# arduino_uno_pcb__with_lcd.net
KiCad netlist of a schematic drawn in EAGLE
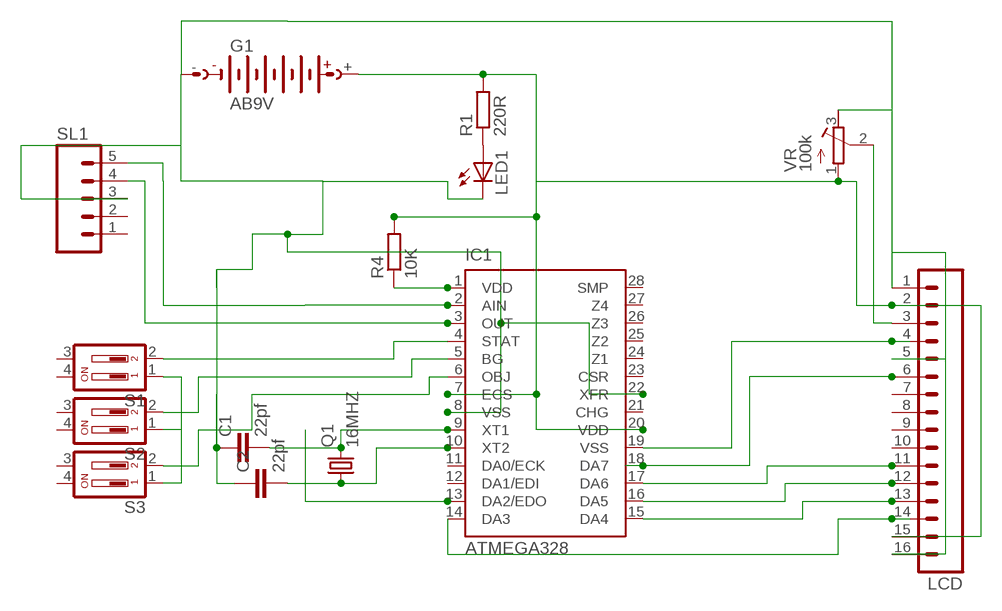
[diagram p0: schematic, sheet 1]

(export (version "E")
  (design (tool "Eeschema 10.0.6"))
  (components
    (comp (ref "C1")
      (value "22pf")
      (footprint "eagle-import:C2.5-2")
      (libsource (lib "eagle-import") (part "C2.5/2"))
    )
    (comp (ref "C2")
      (value "22pf")
      (footprint "eagle-import:C2.5-2")
      (libsource (lib "eagle-import") (part "C2.5/2"))
    )
    (comp (ref "G1")
      (value "AB9V")
      (footprint "eagle-import:AB9V")
      (libsource (lib "eagle-import") (part "AB9V"))
    )
    (comp (ref "IC1")
      (value "ATMEGA328")
      (footprint "eagle-import:DIL28-3")
      (libsource (lib "eagle-import") (part "QT9701BD"))
    )
    (comp (ref "LCD")
      (value "M16")
      (footprint "eagle-import:16P")
      (libsource (lib "eagle-import") (part "M16"))
    )
    (comp (ref "LED1")
      (value "LED3MM")
      (footprint "eagle-import:LED3MM")
      (libsource (lib "eagle-import") (part "LED3MM"))
    )
    (comp (ref "Q1")
      (value "16MHZ")
      (footprint "eagle-import:HC49_S")
      (libsource (lib "eagle-import") (part "CRYSTALHC49S"))
    )
    (comp (ref "R1")
      (value "220R")
      (footprint "eagle-import:0207_10")
      (libsource (lib "eagle-import") (part "R-EU_0207/10"))
    )
    (comp (ref "R4")
      (value "10K")
      (footprint "eagle-import:0207_10")
      (libsource (lib "eagle-import") (part "R-EU_0207/10"))
    )
    (comp (ref "S1")
      (value "DP02")
      (footprint "eagle-import:DP-02")
      (fields (field (name "MPN") "MCDP02"))
      (libsource (lib "eagle-import") (part "DP02"))
    )
    (comp (ref "S2")
      (value "DP02")
      (footprint "eagle-import:DP-02")
      (fields
        (field (name "MPN") "MCDP02")
        (field (name "MPN_1") "MCDP02")
        (field (name "OC_FARNELL") "1255233")
        (field (name "OC_NEWARK") "26M1095")
      )
      (libsource (lib "eagle-import") (part "DP02"))
    )
    (comp (ref "S3")
      (value "DP02")
      (footprint "eagle-import:DP-02")
      (fields
        (field (name "MPN") "MCDP02")
        (field (name "MPN_1") "MCDP02")
        (field (name "OC_FARNELL") "1255233")
        (field (name "OC_NEWARK") "26M1095")
      )
      (libsource (lib "eagle-import") (part "DP02"))
    )
    (comp (ref "SL1")
      (value "M05")
      (footprint "eagle-import:05P")
      (libsource (lib "eagle-import") (part "M05"))
    )
    (comp (ref "VR")
      (value "100k")
      (footprint "eagle-import:RTRIM64P")
      (libsource (lib "eagle-import") (part "R-TRIMM64P"))
    )
  )
  (nets
    (net (code "1") (name "Net-(IC1-AIN)") (class "Default")
      (node (ref "IC1") (pin "2") (pinfunction "AIN_2") (pintype "input"))
      (node (ref "SL1") (pin "5") (pinfunction "5_5") (pintype "passive"))
    )
    (net (code "2") (name "Net-(IC1-BG)") (class "Default")
      (node (ref "IC1") (pin "5") (pinfunction "BG_5") (pintype "input"))
      (node (ref "S2") (pin "2") (pinfunction "2_2") (pintype "passive"))
    )
    (net (code "3") (name "Net-(IC1-DA3)") (class "Default")
      (node (ref "IC1") (pin "14") (pinfunction "DA3_14") (pintype "output"))
      (node (ref "LCD") (pin "14") (pinfunction "14_14") (pintype "passive"))
    )
    (net (code "4") (name "Net-(IC1-DA4)") (class "Default")
      (node (ref "IC1") (pin "15") (pinfunction "DA4_15") (pintype "output"))
      (node (ref "LCD") (pin "13") (pinfunction "13_13") (pintype "passive"))
    )
    (net (code "5") (name "Net-(IC1-DA5)") (class "Default")
      (node (ref "IC1") (pin "16") (pinfunction "DA5_16") (pintype "output"))
      (node (ref "LCD") (pin "12") (pinfunction "12_12") (pintype "passive"))
    )
    (net (code "6") (name "Net-(IC1-DA6)") (class "Default")
      (node (ref "IC1") (pin "17") (pinfunction "DA6_17") (pintype "output"))
      (node (ref "LCD") (pin "11") (pinfunction "11_11") (pintype "passive"))
    )
    (net (code "7") (name "Net-(IC1-DA7)") (class "Default")
      (node (ref "IC1") (pin "18") (pinfunction "DA7_18") (pintype "output"))
      (node (ref "LCD") (pin "6") (pinfunction "6_6") (pintype "passive"))
    )
    (net (code "8") (name "Net-(IC1-ECS)") (class "Default")
      (node (ref "G1") (pin "+") (pinfunction "+_+") (pintype "passive"))
      (node (ref "IC1") (pin "20") (pinfunction "VDD_20") (pintype "input"))
      (node (ref "IC1") (pin "7") (pinfunction "ECS_7") (pintype "output"))
      (node (ref "LCD") (pin "15") (pinfunction "15_15") (pintype "passive"))
      (node (ref "LCD") (pin "2") (pinfunction "2_2") (pintype "passive"))
      (node (ref "R1") (pin "2") (pinfunction "2_2") (pintype "passive"))
      (node (ref "R4") (pin "2") (pinfunction "2_2") (pintype "passive"))
      (node (ref "VR") (pin "1") (pinfunction "E_1") (pintype "passive"))
    )
    (net (code "9") (name "Net-(IC1-OBJ)") (class "Default")
      (node (ref "IC1") (pin "6") (pinfunction "OBJ_6") (pintype "input"))
      (node (ref "S3") (pin "2") (pinfunction "2_2") (pintype "passive"))
    )
    (net (code "10") (name "Net-(IC1-OUT)") (class "Default")
      (node (ref "IC1") (pin "3") (pinfunction "OUT_3") (pintype "output"))
      (node (ref "SL1") (pin "4") (pinfunction "4_4") (pintype "passive"))
    )
    (net (code "11") (name "Net-(IC1-STAT)") (class "Default")
      (node (ref "IC1") (pin "4") (pinfunction "STAT_4") (pintype "output"))
      (node (ref "S1") (pin "2") (pinfunction "2_2") (pintype "passive"))
    )
    (net (code "12") (name "Net-(IC1-VDD-Pad1)") (class "Default")
      (node (ref "IC1") (pin "1") (pinfunction "VDD_1") (pintype "input"))
      (node (ref "R4") (pin "1") (pinfunction "1_1") (pintype "passive"))
    )
    (net (code "13") (name "Net-(IC1-VSS-Pad19)") (class "Default")
      (node (ref "IC1") (pin "19") (pinfunction "VSS_19") (pintype "input"))
      (node (ref "LCD") (pin "4") (pinfunction "4_4") (pintype "passive"))
    )
    (net (code "14") (name "Net-(IC1-XFR)") (class "Default")
      (node (ref "C1") (pin "1") (pinfunction "1_1") (pintype "passive"))
      (node (ref "C2") (pin "1") (pinfunction "1_1") (pintype "passive"))
      (node (ref "G1") (pin "-") (pinfunction "-_-") (pintype "passive"))
      (node (ref "IC1") (pin "22") (pinfunction "XFR_22") (pintype "output"))
      (node (ref "IC1") (pin "8") (pinfunction "VSS_8") (pintype "input"))
      (node (ref "LCD") (pin "1") (pinfunction "1_1") (pintype "passive"))
      (node (ref "LCD") (pin "16") (pinfunction "16_16") (pintype "passive"))
      (node (ref "LCD") (pin "5") (pinfunction "5_5") (pintype "passive"))
      (node (ref "LED1") (pin "K") (pinfunction "C_K") (pintype "passive"))
      (node (ref "SL1") (pin "3") (pinfunction "3_3") (pintype "passive"))
      (node (ref "VR") (pin "3") (pinfunction "A_3") (pintype "passive"))
    )
    (net (code "15") (name "Net-(IC1-XT1)") (class "Default")
      (node (ref "C1") (pin "2") (pinfunction "2_2") (pintype "passive"))
      (node (ref "IC1") (pin "9") (pinfunction "XT1_9") (pintype "input"))
      (node (ref "Q1") (pin "2") (pinfunction "2_2") (pintype "passive"))
    )
    (net (code "16") (name "Net-(IC1-XT2)") (class "Default")
      (node (ref "C2") (pin "2") (pinfunction "2_2") (pintype "passive"))
      (node (ref "IC1") (pin "10") (pinfunction "XT2_10") (pintype "output"))
      (node (ref "Q1") (pin "1") (pinfunction "1_1") (pintype "passive"))
    )
    (net (code "17") (name "Net-(LED1-PadA)") (class "Default")
      (node (ref "LED1") (pin "A") (pinfunction "A_A") (pintype "passive"))
      (node (ref "R1") (pin "1") (pinfunction "1_1") (pintype "passive"))
    )
    (net (code "18") (name "Net-(S1-Pad1)") (class "Default")
      (node (ref "S1") (pin "1") (pinfunction "1_1") (pintype "passive"))
      (node (ref "S2") (pin "1") (pinfunction "1_1") (pintype "passive"))
      (node (ref "S3") (pin "1") (pinfunction "1_1") (pintype "passive"))
    )
    (net (code "19") (name "Net-(VR-S)") (class "Default")
      (node (ref "LCD") (pin "3") (pinfunction "3_3") (pintype "passive"))
      (node (ref "VR") (pin "2") (pinfunction "S_2") (pintype "passive"))
    )
    (net (code "20") (name "unconnected-(IC1-CHG-Pad21)") (class "Default")
      (node (ref "IC1") (pin "21") (pinfunction "CHG_21") (pintype "output"))
    )
    (net (code "21") (name "unconnected-(IC1-CSR-Pad23)") (class "Default")
      (node (ref "IC1") (pin "23") (pinfunction "CSR_23") (pintype "output"))
    )
    (net (code "22") (name "unconnected-(IC1-DA0{slash}ECK-Pad11)") (class "Default")
      (node (ref "IC1") (pin "11") (pinfunction "DA0/ECK_11") (pintype "output"))
    )
    (net (code "23") (name "unconnected-(IC1-DA1{slash}EDI-Pad12)") (class "Default")
      (node (ref "IC1") (pin "12") (pinfunction "DA1/EDI_12") (pintype "output"))
    )
    (net (code "24") (name "unconnected-(IC1-DA2{slash}EDO-Pad13)") (class "Default")
      (node (ref "IC1") (pin "13") (pinfunction "DA2/EDO_13") (pintype "output"))
    )
    (net (code "25") (name "unconnected-(IC1-SMP-Pad28)") (class "Default")
      (node (ref "IC1") (pin "28") (pinfunction "SMP_28") (pintype "output"))
    )
    (net (code "26") (name "unconnected-(IC1-Z1-Pad24)") (class "Default")
      (node (ref "IC1") (pin "24") (pinfunction "Z1_24") (pintype "output"))
    )
    (net (code "27") (name "unconnected-(IC1-Z2-Pad25)") (class "Default")
      (node (ref "IC1") (pin "25") (pinfunction "Z2_25") (pintype "output"))
    )
    (net (code "28") (name "unconnected-(IC1-Z3-Pad26)") (class "Default")
      (node (ref "IC1") (pin "26") (pinfunction "Z3_26") (pintype "output"))
    )
    (net (code "29") (name "unconnected-(IC1-Z4-Pad27)") (class "Default")
      (node (ref "IC1") (pin "27") (pinfunction "Z4_27") (pintype "output"))
    )
    (net (code "30") (name "unconnected-(LCD-Pad7)") (class "Default")
      (node (ref "LCD") (pin "7") (pinfunction "7_7") (pintype "passive"))
    )
    (net (code "31") (name "unconnected-(LCD-Pad8)") (class "Default")
      (node (ref "LCD") (pin "8") (pinfunction "8_8") (pintype "passive"))
    )
    (net (code "32") (name "unconnected-(LCD-Pad9)") (class "Default")
      (node (ref "LCD") (pin "9") (pinfunction "9_9") (pintype "passive"))
    )
    (net (code "33") (name "unconnected-(LCD-Pad10)") (class "Default")
      (node (ref "LCD") (pin "10") (pinfunction "10_10") (pintype "passive"))
    )
    (net (code "34") (name "unconnected-(S1-Pad3)") (class "Default")
      (node (ref "S1") (pin "3") (pinfunction "3_3") (pintype "passive"))
    )
    (net (code "35") (name "unconnected-(S1-Pad4)") (class "Default")
      (node (ref "S1") (pin "4") (pinfunction "4_4") (pintype "passive"))
    )
    (net (code "36") (name "unconnected-(S2-Pad3)") (class "Default")
      (node (ref "S2") (pin "3") (pinfunction "3_3") (pintype "passive"))
    )
    (net (code "37") (name "unconnected-(S2-Pad4)") (class "Default")
      (node (ref "S2") (pin "4") (pinfunction "4_4") (pintype "passive"))
    )
    (net (code "38") (name "unconnected-(S3-Pad3)") (class "Default")
      (node (ref "S3") (pin "3") (pinfunction "3_3") (pintype "passive"))
    )
    (net (code "39") (name "unconnected-(S3-Pad4)") (class "Default")
      (node (ref "S3") (pin "4") (pinfunction "4_4") (pintype "passive"))
    )
    (net (code "40") (name "unconnected-(SL1-Pad1)") (class "Default")
      (node (ref "SL1") (pin "1") (pinfunction "1_1") (pintype "passive"))
    )
    (net (code "41") (name "unconnected-(SL1-Pad2)") (class "Default")
      (node (ref "SL1") (pin "2") (pinfunction "2_2") (pintype "passive"))
    )
  )
)
